# FDC.net
KiCad netlist of a schematic drawn in Altium Designer
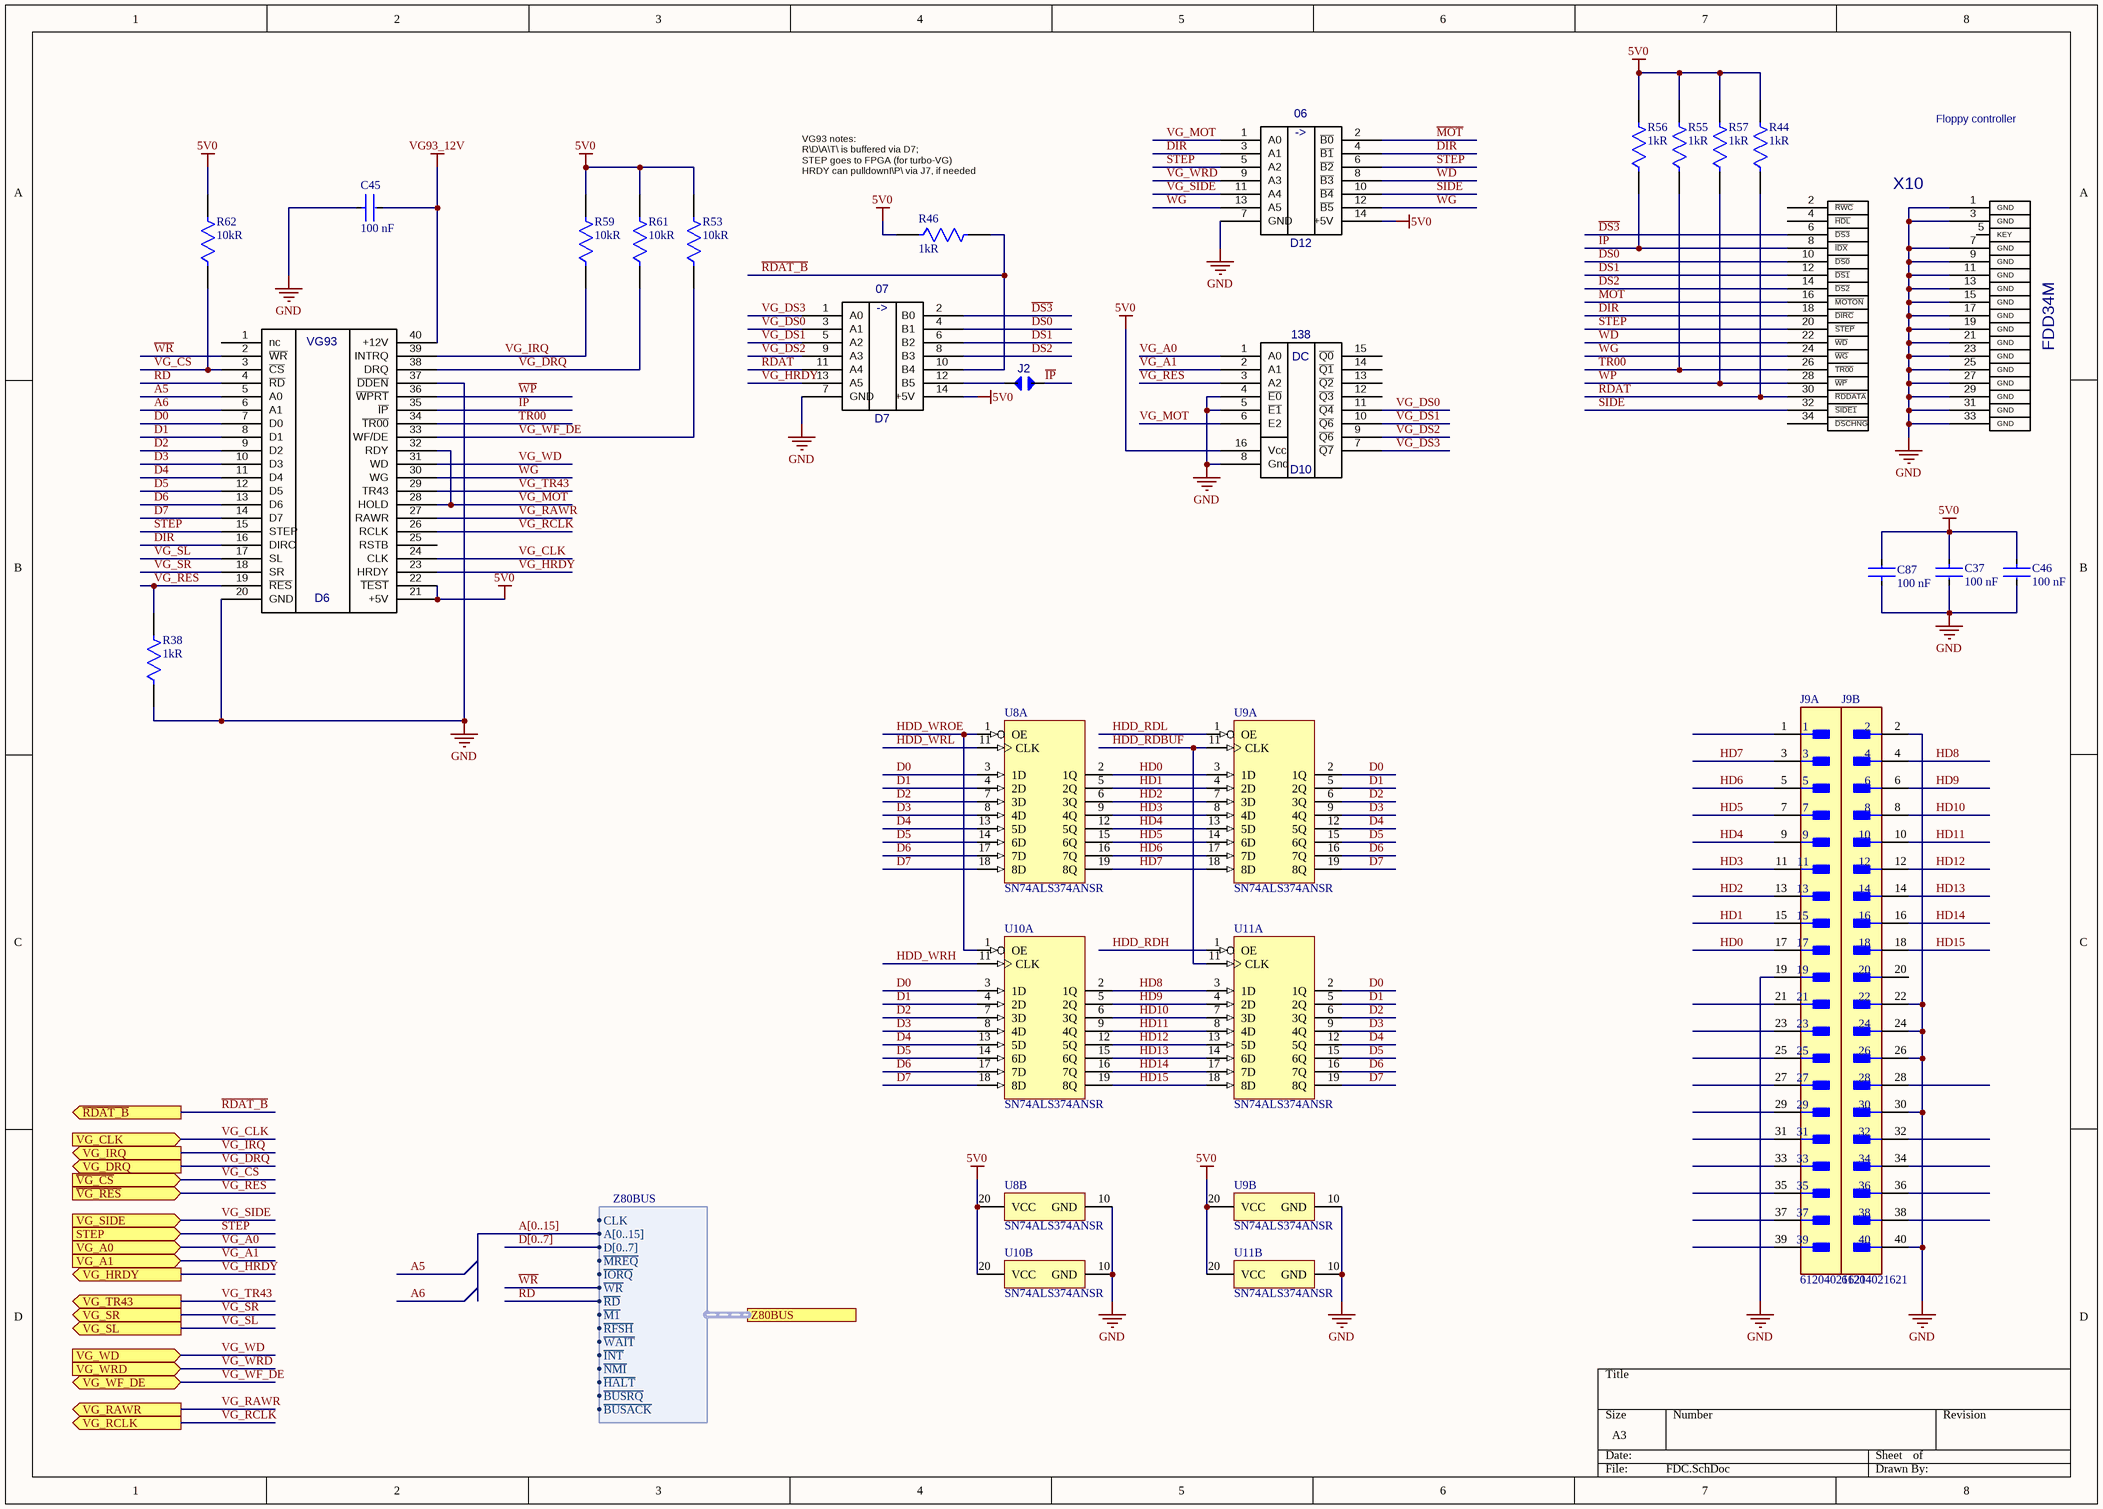
[diagram p0: FDC.SchDoc]

(export (version "E")
  (design (tool "Eeschema 10.0.6"))
  (components
    (comp (ref "C37")
      (value "CC0805KRX7R9BB104")
      (footprint "FP-CC0805-0_85-IPC_A")
      (description "CAP CER 0.1UF 50V X7R 0805")
      (fields (field (name "CAPACITANCE") "100 nF") (field (name "MANUFACTURER") "Yageo"))
      (libsource (lib "SchLib") (part "CMP-2100-03606-3"))
    )
    (comp (ref "C45")
      (value "CC0805KRX7R9BB104")
      (footprint "FP-CC0805-0_85-IPC_A")
      (description "CAP CER 0.1UF 50V X7R 0805")
      (fields (field (name "CAPACITANCE") "100 nF") (field (name "MANUFACTURER") "Yageo"))
      (libsource (lib "SchLib") (part "CMP-2100-03606-3"))
    )
    (comp (ref "C46")
      (value "CC0805KRX7R9BB104")
      (footprint "FP-CC0805-0_85-IPC_A")
      (description "CAP CER 0.1UF 50V X7R 0805")
      (fields (field (name "CAPACITANCE") "100 nF") (field (name "MANUFACTURER") "Yageo"))
      (libsource (lib "SchLib") (part "CMP-2100-03606-3"))
    )
    (comp (ref "C87")
      (value "CC0805KRX7R9BB104")
      (footprint "FP-CC0805-0_85-IPC_A")
      (description "CAP CER 0.1UF 50V X7R 0805")
      (fields (field (name "CAPACITANCE") "100 nF") (field (name "MANUFACTURER") "Yageo"))
      (libsource (lib "SchLib") (part "CMP-2100-03606-3"))
    )
    (comp (ref "D6") (value "KR1818VG93") (footprint "DIP40") (libsource (lib "SchLib") (part "KR1818VG93")))
    (comp (ref "D7") (value "07") (footprint "SO14") (libsource (lib "SchLib") (part "07")))
    (comp (ref "D10") (value "138") (footprint "SO16") (libsource (lib "SchLib") (part "138")))
    (comp (ref "D12") (value "06") (footprint "SO14") (libsource (lib "SchLib") (part "06")))
    (comp (ref "J2")
      (value "JUMPER")
      (footprint "JUMPER_JUMPER(Primary)")
      (description "HLT->~IP")
      (libsource (lib "SchLib") (part "JUMPER"))
    )
    (comp (ref "J9")
      (value "61204021621")
      (footprint "FP-61204021621-MFG")
      (description "CONN HEADER VERT 40POS 2.54MM")
      (libsource (lib "Altium Content Vault") (part "48b0ace1069a9a2e6490059f1444f9e"))
    )
    (comp (ref "R38")
      (value "CRCW08051K00FKEAHP")
      (footprint "FP-CRCW0805-HPe3-IPC_A")
      (description "RES Thick Film, 1kΩ, 1%, 0.5W, 100ppm/°C, 0805")
      (fields (field (name "RESISTANCE") "1kR") (field (name "MANUFACTURER") "Vishay Dale"))
      (libsource (lib "SchLib") (part "CMP-02407-004529-1"))
    )
    (comp (ref "R44")
      (value "CRCW08051K00FKEAHP")
      (footprint "FP-CRCW0805-HPe3-IPC_A")
      (description "RES Thick Film, 1kΩ, 1%, 0.5W, 100ppm/°C, 0805")
      (fields (field (name "RESISTANCE") "1kR") (field (name "MANUFACTURER") "Vishay Dale"))
      (libsource (lib "SchLib") (part "CMP-02407-004529-1"))
    )
    (comp (ref "R46")
      (value "CRCW08051K00FKEAHP")
      (footprint "FP-CRCW0805-HPe3-IPC_A")
      (description "RES Thick Film, 1kΩ, 1%, 0.5W, 100ppm/°C, 0805")
      (fields (field (name "RESISTANCE") "1kR") (field (name "MANUFACTURER") "Vishay Dale"))
      (libsource (lib "SchLib") (part "CMP-02407-004529-1"))
    )
    (comp (ref "R53")
      (value "CR0805-JW-103ELF")
      (footprint "FP-CR0805-IPC_A")
      (description "Thick Film Chip Resistors 0805 10kΩ 0.125W 5% 200ppm/°C")
      (fields (field (name "RESISTANCE") "10kR") (field (name "MANUFACTURER") "Bourns"))
      (libsource (lib "SchLib") (part "CMP-07231-003873-1"))
    )
    (comp (ref "R55")
      (value "CRCW08051K00FKEAHP")
      (footprint "FP-CRCW0805-HPe3-IPC_A")
      (description "RES Thick Film, 1kΩ, 1%, 0.5W, 100ppm/°C, 0805")
      (fields (field (name "RESISTANCE") "1kR") (field (name "MANUFACTURER") "Vishay Dale"))
      (libsource (lib "SchLib") (part "CMP-02407-004529-1"))
    )
    (comp (ref "R56")
      (value "CRCW08051K00FKEAHP")
      (footprint "FP-CRCW0805-HPe3-IPC_A")
      (description "RES Thick Film, 1kΩ, 1%, 0.5W, 100ppm/°C, 0805")
      (fields (field (name "RESISTANCE") "1kR") (field (name "MANUFACTURER") "Vishay Dale"))
      (libsource (lib "SchLib") (part "CMP-02407-004529-1"))
    )
    (comp (ref "R57")
      (value "CRCW08051K00FKEAHP")
      (footprint "FP-CRCW0805-HPe3-IPC_A")
      (description "RES Thick Film, 1kΩ, 1%, 0.5W, 100ppm/°C, 0805")
      (fields (field (name "RESISTANCE") "1kR") (field (name "MANUFACTURER") "Vishay Dale"))
      (libsource (lib "SchLib") (part "CMP-02407-004529-1"))
    )
    (comp (ref "R59")
      (value "CR0805-JW-103ELF")
      (footprint "FP-CR0805-IPC_A")
      (description "Thick Film Chip Resistors 0805 10kΩ 0.125W 5% 200ppm/°C")
      (fields (field (name "RESISTANCE") "10kR") (field (name "MANUFACTURER") "Bourns"))
      (libsource (lib "SchLib") (part "CMP-07231-003873-1"))
    )
    (comp (ref "R61")
      (value "CR0805-JW-103ELF")
      (footprint "FP-CR0805-IPC_A")
      (description "Thick Film Chip Resistors 0805 10kΩ 0.125W 5% 200ppm/°C")
      (fields (field (name "RESISTANCE") "10kR") (field (name "MANUFACTURER") "Bourns"))
      (libsource (lib "SchLib") (part "CMP-07231-003873-1"))
    )
    (comp (ref "R62")
      (value "CR0805-JW-103ELF")
      (footprint "FP-CR0805-IPC_A")
      (description "Thick Film Chip Resistors 0805 10kΩ 0.125W 5% 200ppm/°C")
      (fields (field (name "RESISTANCE") "10kR") (field (name "MANUFACTURER") "Bourns"))
      (libsource (lib "SchLib") (part "CMP-07231-003873-1"))
    )
    (comp (ref "U8")
      (value "SN74ALS374ANSR")
      (footprint "NS0020A_M")
      (description "Octal D-Type Edge Triggered Flip-Flops with 3-State Outputs, NS0020A, LARGE T&R")
      (fields
        (field (name "GENERIC PART NUMBER") "SN74ALS374A")
        (field (name "MANUFACTURER") "Texas Instruments")
      )
      (libsource (lib "Altium Content Vault") (part "TI-CD_SNX4XXXXX374X-20"))
    )
    (comp (ref "U9")
      (value "SN74ALS374ANSR")
      (footprint "NS0020A_M")
      (description "Octal D-Type Edge Triggered Flip-Flops with 3-State Outputs, NS0020A, LARGE T&R")
      (fields
        (field (name "GENERIC PART NUMBER") "SN74ALS374A")
        (field (name "MANUFACTURER") "Texas Instruments")
      )
      (libsource (lib "Altium Content Vault") (part "TI-CD_SNX4XXXXX374X-20"))
    )
    (comp (ref "U10")
      (value "SN74ALS374ANSR")
      (footprint "NS0020A_M")
      (description "Octal D-Type Edge Triggered Flip-Flops with 3-State Outputs, NS0020A, LARGE T&R")
      (fields
        (field (name "GENERIC PART NUMBER") "SN74ALS374A")
        (field (name "MANUFACTURER") "Texas Instruments")
      )
      (libsource (lib "Altium Content Vault") (part "TI-CD_SNX4XXXXX374X-20"))
    )
    (comp (ref "U11")
      (value "SN74ALS374ANSR")
      (footprint "NS0020A_M")
      (description "Octal D-Type Edge Triggered Flip-Flops with 3-State Outputs, NS0020A, LARGE T&R")
      (fields
        (field (name "GENERIC PART NUMBER") "SN74ALS374A")
        (field (name "MANUFACTURER") "Texas Instruments")
      )
      (libsource (lib "Altium Content Vault") (part "TI-CD_SNX4XXXXX374X-20"))
    )
    (comp (ref "X10") (value "FDD34M") (footprint "FDD34M") (libsource (lib "SchLib") (part "FDD34M")))
  )
  (nets
    (net (code "16") (name "/A5") (class "Default")
      (node (ref "D6") (pin "5") (pinfunction "A0_5") (pintype "passive"))
    )
    (net (code "17") (name "/A6") (class "Default")
      (node (ref "D6") (pin "6") (pinfunction "A1_6") (pintype "passive"))
    )
    (net (code "19") (name "/D0") (class "Default")
      (node (ref "D6") (pin "7") (pinfunction "D0_7") (pintype "passive"))
      (node (ref "U10") (pin "3") (pinfunction "1D_3") (pintype "input"))
      (node (ref "U11") (pin "2") (pinfunction "1Q_2") (pintype "tri_state"))
      (node (ref "U8") (pin "3") (pinfunction "1D_3") (pintype "input"))
      (node (ref "U9") (pin "2") (pinfunction "1Q_2") (pintype "tri_state"))
    )
    (net (code "20") (name "/D1") (class "Default")
      (node (ref "D6") (pin "8") (pinfunction "D1_8") (pintype "passive"))
      (node (ref "U10") (pin "4") (pinfunction "2D_4") (pintype "input"))
      (node (ref "U11") (pin "5") (pinfunction "2Q_5") (pintype "tri_state"))
      (node (ref "U8") (pin "4") (pinfunction "2D_4") (pintype "input"))
      (node (ref "U9") (pin "5") (pinfunction "2Q_5") (pintype "tri_state"))
    )
    (net (code "21") (name "/D2") (class "Default")
      (node (ref "D6") (pin "9") (pinfunction "D2_9") (pintype "passive"))
      (node (ref "U10") (pin "7") (pinfunction "3D_7") (pintype "input"))
      (node (ref "U11") (pin "6") (pinfunction "3Q_6") (pintype "tri_state"))
      (node (ref "U8") (pin "7") (pinfunction "3D_7") (pintype "input"))
      (node (ref "U9") (pin "6") (pinfunction "3Q_6") (pintype "tri_state"))
    )
    (net (code "22") (name "/D3") (class "Default")
      (node (ref "D6") (pin "10") (pinfunction "D3_10") (pintype "passive"))
      (node (ref "U10") (pin "8") (pinfunction "4D_8") (pintype "input"))
      (node (ref "U11") (pin "9") (pinfunction "4Q_9") (pintype "tri_state"))
      (node (ref "U8") (pin "8") (pinfunction "4D_8") (pintype "input"))
      (node (ref "U9") (pin "9") (pinfunction "4Q_9") (pintype "tri_state"))
    )
    (net (code "23") (name "/D4") (class "Default")
      (node (ref "D6") (pin "11") (pinfunction "D4_11") (pintype "passive"))
      (node (ref "U10") (pin "13") (pinfunction "5D_13") (pintype "input"))
      (node (ref "U11") (pin "12") (pinfunction "5Q_12") (pintype "tri_state"))
      (node (ref "U8") (pin "13") (pinfunction "5D_13") (pintype "input"))
      (node (ref "U9") (pin "12") (pinfunction "5Q_12") (pintype "tri_state"))
    )
    (net (code "24") (name "/D5") (class "Default")
      (node (ref "D6") (pin "12") (pinfunction "D5_12") (pintype "passive"))
      (node (ref "U10") (pin "14") (pinfunction "6D_14") (pintype "input"))
      (node (ref "U11") (pin "15") (pinfunction "6Q_15") (pintype "tri_state"))
      (node (ref "U8") (pin "14") (pinfunction "6D_14") (pintype "input"))
      (node (ref "U9") (pin "15") (pinfunction "6Q_15") (pintype "tri_state"))
    )
    (net (code "25") (name "/D6") (class "Default")
      (node (ref "D6") (pin "13") (pinfunction "D6_13") (pintype "passive"))
      (node (ref "U10") (pin "17") (pinfunction "7D_17") (pintype "input"))
      (node (ref "U11") (pin "16") (pinfunction "7Q_16") (pintype "tri_state"))
      (node (ref "U8") (pin "17") (pinfunction "7D_17") (pintype "input"))
      (node (ref "U9") (pin "16") (pinfunction "7Q_16") (pintype "tri_state"))
    )
    (net (code "26") (name "/D7") (class "Default")
      (node (ref "D6") (pin "14") (pinfunction "D7_14") (pintype "passive"))
      (node (ref "U10") (pin "18") (pinfunction "8D_18") (pintype "input"))
      (node (ref "U11") (pin "19") (pinfunction "8Q_19") (pintype "tri_state"))
      (node (ref "U8") (pin "18") (pinfunction "8D_18") (pintype "input"))
      (node (ref "U9") (pin "19") (pinfunction "8Q_19") (pintype "tri_state"))
    )
    (net (code "27") (name "/DIR") (class "Default")
      (node (ref "D12") (pin "3") (pinfunction "A1_3") (pintype "passive"))
      (node (ref "D6") (pin "16") (pinfunction "DIRC_16") (pintype "passive"))
    )
    (net (code "28") (name "/HD0") (class "Default")
      (node (ref "J9") (pin "17") (pinfunction "17_17") (pintype "passive"))
      (node (ref "U8") (pin "2") (pinfunction "1Q_2") (pintype "tri_state"))
      (node (ref "U9") (pin "3") (pinfunction "1D_3") (pintype "input"))
    )
    (net (code "29") (name "/HD1") (class "Default")
      (node (ref "J9") (pin "15") (pinfunction "15_15") (pintype "passive"))
      (node (ref "U8") (pin "5") (pinfunction "2Q_5") (pintype "tri_state"))
      (node (ref "U9") (pin "4") (pinfunction "2D_4") (pintype "input"))
    )
    (net (code "30") (name "/HD2") (class "Default")
      (node (ref "J9") (pin "13") (pinfunction "13_13") (pintype "passive"))
      (node (ref "U8") (pin "6") (pinfunction "3Q_6") (pintype "tri_state"))
      (node (ref "U9") (pin "7") (pinfunction "3D_7") (pintype "input"))
    )
    (net (code "31") (name "/HD3") (class "Default")
      (node (ref "J9") (pin "11") (pinfunction "11_11") (pintype "passive"))
      (node (ref "U8") (pin "9") (pinfunction "4Q_9") (pintype "tri_state"))
      (node (ref "U9") (pin "8") (pinfunction "4D_8") (pintype "input"))
    )
    (net (code "32") (name "/HD4") (class "Default")
      (node (ref "J9") (pin "9") (pinfunction "9_9") (pintype "passive"))
      (node (ref "U8") (pin "12") (pinfunction "5Q_12") (pintype "tri_state"))
      (node (ref "U9") (pin "13") (pinfunction "5D_13") (pintype "input"))
    )
    (net (code "33") (name "/HD5") (class "Default")
      (node (ref "J9") (pin "7") (pinfunction "7_7") (pintype "passive"))
      (node (ref "U8") (pin "15") (pinfunction "6Q_15") (pintype "tri_state"))
      (node (ref "U9") (pin "14") (pinfunction "6D_14") (pintype "input"))
    )
    (net (code "34") (name "/HD6") (class "Default")
      (node (ref "J9") (pin "5") (pinfunction "5_5") (pintype "passive"))
      (node (ref "U8") (pin "16") (pinfunction "7Q_16") (pintype "tri_state"))
      (node (ref "U9") (pin "17") (pinfunction "7D_17") (pintype "input"))
    )
    (net (code "35") (name "/HD7") (class "Default")
      (node (ref "J9") (pin "3") (pinfunction "3_3") (pintype "passive"))
      (node (ref "U8") (pin "19") (pinfunction "8Q_19") (pintype "tri_state"))
      (node (ref "U9") (pin "18") (pinfunction "8D_18") (pintype "input"))
    )
    (net (code "36") (name "/HD8") (class "Default")
      (node (ref "J9") (pin "4") (pinfunction "4_4") (pintype "passive"))
      (node (ref "U10") (pin "2") (pinfunction "1Q_2") (pintype "tri_state"))
      (node (ref "U11") (pin "3") (pinfunction "1D_3") (pintype "input"))
    )
    (net (code "37") (name "/HD9") (class "Default")
      (node (ref "J9") (pin "6") (pinfunction "6_6") (pintype "passive"))
      (node (ref "U10") (pin "5") (pinfunction "2Q_5") (pintype "tri_state"))
      (node (ref "U11") (pin "4") (pinfunction "2D_4") (pintype "input"))
    )
    (net (code "38") (name "/HD10") (class "Default")
      (node (ref "J9") (pin "8") (pinfunction "8_8") (pintype "passive"))
      (node (ref "U10") (pin "6") (pinfunction "3Q_6") (pintype "tri_state"))
      (node (ref "U11") (pin "7") (pinfunction "3D_7") (pintype "input"))
    )
    (net (code "39") (name "/HD11") (class "Default")
      (node (ref "J9") (pin "10") (pinfunction "10_10") (pintype "passive"))
      (node (ref "U10") (pin "9") (pinfunction "4Q_9") (pintype "tri_state"))
      (node (ref "U11") (pin "8") (pinfunction "4D_8") (pintype "input"))
    )
    (net (code "40") (name "/HD12") (class "Default")
      (node (ref "J9") (pin "12") (pinfunction "12_12") (pintype "passive"))
      (node (ref "U10") (pin "12") (pinfunction "5Q_12") (pintype "tri_state"))
      (node (ref "U11") (pin "13") (pinfunction "5D_13") (pintype "input"))
    )
    (net (code "41") (name "/HD13") (class "Default")
      (node (ref "J9") (pin "14") (pinfunction "14_14") (pintype "passive"))
      (node (ref "U10") (pin "15") (pinfunction "6Q_15") (pintype "tri_state"))
      (node (ref "U11") (pin "14") (pinfunction "6D_14") (pintype "input"))
    )
    (net (code "42") (name "/HD14") (class "Default")
      (node (ref "J9") (pin "16") (pinfunction "16_16") (pintype "passive"))
      (node (ref "U10") (pin "16") (pinfunction "7Q_16") (pintype "tri_state"))
      (node (ref "U11") (pin "17") (pinfunction "7D_17") (pintype "input"))
    )
    (net (code "43") (name "/HD15") (class "Default")
      (node (ref "J9") (pin "18") (pinfunction "18_18") (pintype "passive"))
      (node (ref "U10") (pin "19") (pinfunction "8Q_19") (pintype "tri_state"))
      (node (ref "U11") (pin "18") (pinfunction "8D_18") (pintype "input"))
    )
    (net (code "44") (name "/HDD_RDBUF") (class "Default")
      (node (ref "U11") (pin "11") (pinfunction "CLK_11") (pintype "input"))
      (node (ref "U9") (pin "11") (pinfunction "CLK_11") (pintype "input"))
    )
    (net (code "45") (name "/HDD_RDH") (class "Default")
      (node (ref "U11") (pin "1") (pinfunction "OE_1") (pintype "input"))
    )
    (net (code "46") (name "/HDD_RDL") (class "Default")
      (node (ref "U9") (pin "1") (pinfunction "OE_1") (pintype "input"))
    )
    (net (code "47") (name "/HDD_WRH") (class "Default")
      (node (ref "U10") (pin "11") (pinfunction "CLK_11") (pintype "input"))
    )
    (net (code "48") (name "/HDD_WRL") (class "Default")
      (node (ref "U8") (pin "11") (pinfunction "CLK_11") (pintype "input"))
    )
    (net (code "49") (name "/HDD_WROE") (class "Default")
      (node (ref "U10") (pin "1") (pinfunction "OE_1") (pintype "input"))
      (node (ref "U8") (pin "1") (pinfunction "OE_1") (pintype "input"))
    )
    (net (code "50") (name "/STEP") (class "Default")
      (node (ref "D12") (pin "5") (pinfunction "A2_5") (pintype "passive"))
      (node (ref "D6") (pin "15") (pinfunction "STEP_15") (pintype "passive"))
    )
    (net (code "51") (name "/VG_A0") (class "Default")
      (node (ref "D10") (pin "1") (pinfunction "A0_1") (pintype "passive"))
    )
    (net (code "52") (name "/VG_A1") (class "Default")
      (node (ref "D10") (pin "2") (pinfunction "A1_2") (pintype "passive"))
    )
    (net (code "53") (name "/VG_CLK") (class "Default")
      (node (ref "D6") (pin "24") (pinfunction "CLK_24") (pintype "passive"))
    )
    (net (code "54") (name "/VG_DRQ") (class "Default")
      (node (ref "D6") (pin "38") (pinfunction "DRQ_38") (pintype "passive"))
      (node (ref "R61") (pin "1") (pinfunction "1_1") (pintype "passive"))
    )
    (net (code "55") (name "/VG_DS0") (class "Default")
      (node (ref "D10") (pin "11") (pinfunction "~{Q4}_11") (pintype "passive"))
      (node (ref "D7") (pin "3") (pinfunction "A1_3") (pintype "passive"))
    )
    (net (code "56") (name "/VG_DS1") (class "Default")
      (node (ref "D10") (pin "10") (pinfunction "~{Q6}_10") (pintype "passive"))
      (node (ref "D7") (pin "5") (pinfunction "A2_5") (pintype "passive"))
    )
    (net (code "57") (name "/VG_DS2") (class "Default")
      (node (ref "D10") (pin "9") (pinfunction "~{Q6}_9") (pintype "passive"))
      (node (ref "D7") (pin "9") (pinfunction "A3_9") (pintype "passive"))
    )
    (net (code "58") (name "/VG_DS3") (class "Default")
      (node (ref "D10") (pin "7") (pinfunction "~{Q7}_7") (pintype "passive"))
      (node (ref "D7") (pin "1") (pinfunction "A0_1") (pintype "passive"))
    )
    (net (code "59") (name "/VG_HRDY") (class "Default")
      (node (ref "D6") (pin "23") (pinfunction "HRDY_23") (pintype "passive"))
      (node (ref "D7") (pin "13") (pinfunction "A5_13") (pintype "passive"))
    )
    (net (code "60") (name "/VG_IRQ") (class "Default")
      (node (ref "D6") (pin "39") (pinfunction "INTRQ_39") (pintype "passive"))
      (node (ref "R59") (pin "1") (pinfunction "1_1") (pintype "passive"))
    )
    (net (code "61") (name "/VG_MOT") (class "Default")
      (node (ref "D10") (pin "6") (pinfunction "E2_6") (pintype "passive"))
      (node (ref "D12") (pin "1") (pinfunction "A0_1") (pintype "passive"))
      (node (ref "D6") (pin "28") (pinfunction "HOLD_28") (pintype "passive"))
      (node (ref "D6") (pin "32") (pinfunction "RDY_32") (pintype "passive"))
    )
    (net (code "62") (name "/VG_RAWR") (class "Default")
      (node (ref "D6") (pin "27") (pinfunction "RAWR_27") (pintype "passive"))
    )
    (net (code "63") (name "/VG_RCLK") (class "Default")
      (node (ref "D6") (pin "26") (pinfunction "RCLK_26") (pintype "passive"))
    )
    (net (code "64") (name "/VG_SIDE") (class "Default")
      (node (ref "D12") (pin "11") (pinfunction "A4_11") (pintype "passive"))
    )
    (net (code "65") (name "/VG_SL") (class "Default")
      (node (ref "D6") (pin "17") (pinfunction "SL_17") (pintype "passive"))
    )
    (net (code "66") (name "/VG_SR") (class "Default")
      (node (ref "D6") (pin "18") (pinfunction "SR_18") (pintype "passive"))
    )
    (net (code "67") (name "/VG_TR43") (class "Default")
      (node (ref "D6") (pin "29") (pinfunction "TR43_29") (pintype "passive"))
    )
    (net (code "68") (name "/VG_WD") (class "Default")
      (node (ref "D6") (pin "31") (pinfunction "WD_31") (pintype "passive"))
    )
    (net (code "69") (name "/VG_WF_DE") (class "Default")
      (node (ref "D6") (pin "33") (pinfunction "WF/DE_33") (pintype "passive"))
      (node (ref "R53") (pin "1") (pinfunction "1_1") (pintype "passive"))
    )
    (net (code "70") (name "/VG_WRD") (class "Default")
      (node (ref "D12") (pin "9") (pinfunction "A3_9") (pintype "passive"))
    )
    (net (code "71") (name "/WG") (class "Default")
      (node (ref "D12") (pin "13") (pinfunction "A5_13") (pintype "passive"))
      (node (ref "D6") (pin "30") (pinfunction "WG_30") (pintype "passive"))
    )
    (net (code "74") (name "/~{DIR}") (class "Default")
      (node (ref "D12") (pin "4") (pinfunction "~{B1}_4") (pintype "passive"))
      (node (ref "X10") (pin "18") (pinfunction "~{DIRC}_18") (pintype "passive"))
    )
    (net (code "75") (name "/~{DS0}") (class "Default")
      (node (ref "D7") (pin "4") (pinfunction "B1_4") (pintype "passive"))
      (node (ref "X10") (pin "10") (pinfunction "~{DS0}_10") (pintype "passive"))
    )
    (net (code "76") (name "/~{DS1}") (class "Default")
      (node (ref "D7") (pin "6") (pinfunction "B2_6") (pintype "passive"))
      (node (ref "X10") (pin "12") (pinfunction "~{DS1}_12") (pintype "passive"))
    )
    (net (code "77") (name "/~{DS2}") (class "Default")
      (node (ref "D7") (pin "8") (pinfunction "B3_8") (pintype "passive"))
      (node (ref "X10") (pin "14") (pinfunction "~{DS2}_14") (pintype "passive"))
    )
    (net (code "78") (name "/~{DS3}") (class "Default")
      (node (ref "D7") (pin "2") (pinfunction "B0_2") (pintype "passive"))
      (node (ref "X10") (pin "6") (pinfunction "~{DS3}_6") (pintype "passive"))
    )
    (net (code "79") (name "/~{IP}") (class "Default")
      (node (ref "D6") (pin "35") (pinfunction "~{IP}_35") (pintype "passive"))
      (node (ref "J2") (pin "1") (pinfunction "2_1") (pintype "passive"))
      (node (ref "R56") (pin "1") (pinfunction "1_1") (pintype "passive"))
      (node (ref "X10") (pin "8") (pinfunction "~{IDX}_8") (pintype "passive"))
    )
    (net (code "80") (name "/~{MOT}") (class "Default")
      (node (ref "D12") (pin "2") (pinfunction "~{B0}_2") (pintype "passive"))
      (node (ref "X10") (pin "16") (pinfunction "~{MOTON}_16") (pintype "passive"))
    )
    (net (code "81") (name "/~{RDAT_B}") (class "Default")
      (node (ref "D7") (pin "10") (pinfunction "B4_10") (pintype "passive"))
      (node (ref "R46") (pin "2") (pinfunction "2_2") (pintype "passive"))
    )
    (net (code "82") (name "/~{RDAT}") (class "Default")
      (node (ref "D7") (pin "11") (pinfunction "A4_11") (pintype "passive"))
      (node (ref "R44") (pin "1") (pinfunction "1_1") (pintype "passive"))
      (node (ref "X10") (pin "30") (pinfunction "~{RDDATA}_30") (pintype "passive"))
    )
    (net (code "83") (name "/~{RD}") (class "Default")
      (node (ref "D6") (pin "4") (pinfunction "~{RD}_4") (pintype "passive"))
    )
    (net (code "84") (name "/~{SIDE}") (class "Default")
      (node (ref "D12") (pin "10") (pinfunction "~{B4}_10") (pintype "passive"))
      (node (ref "X10") (pin "32") (pinfunction "~{SIDE1}_32") (pintype "passive"))
    )
    (net (code "85") (name "/~{STEP}") (class "Default")
      (node (ref "D12") (pin "6") (pinfunction "~{B2}_6") (pintype "passive"))
      (node (ref "X10") (pin "20") (pinfunction "~{STEP}_20") (pintype "passive"))
    )
    (net (code "86") (name "/~{TR00}") (class "Default")
      (node (ref "D6") (pin "34") (pinfunction "~{TR00}_34") (pintype "passive"))
      (node (ref "R55") (pin "1") (pinfunction "1_1") (pintype "passive"))
      (node (ref "X10") (pin "26") (pinfunction "~{TR00}_26") (pintype "passive"))
    )
    (net (code "87") (name "/~{VG_CS}") (class "Default")
      (node (ref "D6") (pin "3") (pinfunction "~{CS}_3") (pintype "passive"))
      (node (ref "R62") (pin "1") (pinfunction "1_1") (pintype "passive"))
    )
    (net (code "88") (name "/~{VG_RES}") (class "Default")
      (node (ref "D10") (pin "3") (pinfunction "A2_3") (pintype "passive"))
      (node (ref "D6") (pin "19") (pinfunction "~{RES}_19") (pintype "passive"))
      (node (ref "R38") (pin "2") (pinfunction "2_2") (pintype "passive"))
    )
    (net (code "89") (name "/~{WD}") (class "Default")
      (node (ref "D12") (pin "8") (pinfunction "~{B3}_8") (pintype "passive"))
      (node (ref "X10") (pin "22") (pinfunction "~{WD}_22") (pintype "passive"))
    )
    (net (code "90") (name "/~{WG}") (class "Default")
      (node (ref "D12") (pin "12") (pinfunction "~{B5}_12") (pintype "passive"))
      (node (ref "X10") (pin "24") (pinfunction "~{WG}_24") (pintype "passive"))
    )
    (net (code "91") (name "/~{WP}") (class "Default")
      (node (ref "D6") (pin "36") (pinfunction "~{WPRT}_36") (pintype "passive"))
      (node (ref "R57") (pin "1") (pinfunction "1_1") (pintype "passive"))
      (node (ref "X10") (pin "28") (pinfunction "~{WP}_28") (pintype "passive"))
    )
    (net (code "92") (name "/~{WR}") (class "Default")
      (node (ref "D6") (pin "2") (pinfunction "~{WR}_2") (pintype "passive"))
    )
    (net (code "93") (name "5V0") (class "Default")
      (node (ref "C37") (pin "1") (pinfunction "1_1") (pintype "passive"))
      (node (ref "C46") (pin "1") (pinfunction "1_1") (pintype "passive"))
      (node (ref "C87") (pin "2") (pinfunction "2_2") (pintype "passive"))
      (node (ref "D10") (pin "16") (pinfunction "Vcc_16") (pintype "passive"))
      (node (ref "D12") (pin "14") (pinfunction "+5V_14") (pintype "passive"))
      (node (ref "D6") (pin "21") (pinfunction "+5V_21") (pintype "passive"))
      (node (ref "D6") (pin "22") (pinfunction "~{TEST}_22") (pintype "passive"))
      (node (ref "D7") (pin "14") (pinfunction "+5V_14") (pintype "passive"))
      (node (ref "R44") (pin "2") (pinfunction "2_2") (pintype "passive"))
      (node (ref "R46") (pin "1") (pinfunction "1_1") (pintype "passive"))
      (node (ref "R53") (pin "2") (pinfunction "2_2") (pintype "passive"))
      (node (ref "R55") (pin "2") (pinfunction "2_2") (pintype "passive"))
      (node (ref "R56") (pin "2") (pinfunction "2_2") (pintype "passive"))
      (node (ref "R57") (pin "2") (pinfunction "2_2") (pintype "passive"))
      (node (ref "R59") (pin "2") (pinfunction "2_2") (pintype "passive"))
      (node (ref "R61") (pin "2") (pinfunction "2_2") (pintype "passive"))
      (node (ref "R62") (pin "2") (pinfunction "2_2") (pintype "passive"))
      (node (ref "U10") (pin "20") (pinfunction "VCC_20") (pintype "power_in"))
      (node (ref "U11") (pin "20") (pinfunction "VCC_20") (pintype "power_in"))
      (node (ref "U8") (pin "20") (pinfunction "VCC_20") (pintype "power_in"))
      (node (ref "U9") (pin "20") (pinfunction "VCC_20") (pintype "power_in"))
    )
    (net (code "94") (name "GND") (class "Default")
      (node (ref "C37") (pin "2") (pinfunction "2_2") (pintype "passive"))
      (node (ref "C45") (pin "1") (pinfunction "1_1") (pintype "passive"))
      (node (ref "C46") (pin "2") (pinfunction "2_2") (pintype "passive"))
      (node (ref "C87") (pin "1") (pinfunction "1_1") (pintype "passive"))
      (node (ref "D10") (pin "4") (pinfunction "~{E0}_4") (pintype "passive"))
      (node (ref "D10") (pin "5") (pinfunction "~{E1}_5") (pintype "passive"))
      (node (ref "D10") (pin "8") (pinfunction "Gnd_8") (pintype "passive"))
      (node (ref "D12") (pin "7") (pinfunction "GND_7") (pintype "passive"))
      (node (ref "D6") (pin "20") (pinfunction "GND_20") (pintype "passive"))
      (node (ref "D6") (pin "37") (pinfunction "~{DDEN}_37") (pintype "passive"))
      (node (ref "D7") (pin "7") (pinfunction "GND_7") (pintype "passive"))
      (node (ref "J9") (pin "19") (pinfunction "19_19") (pintype "passive"))
      (node (ref "J9") (pin "2") (pinfunction "2_2") (pintype "passive"))
      (node (ref "J9") (pin "22") (pinfunction "22_22") (pintype "passive"))
      (node (ref "J9") (pin "24") (pinfunction "24_24") (pintype "passive"))
      (node (ref "J9") (pin "26") (pinfunction "26_26") (pintype "passive"))
      (node (ref "J9") (pin "30") (pinfunction "30_30") (pintype "passive"))
      (node (ref "J9") (pin "40") (pinfunction "40_40") (pintype "passive"))
      (node (ref "R38") (pin "1") (pinfunction "1_1") (pintype "passive"))
      (node (ref "U10") (pin "10") (pinfunction "GND_10") (pintype "power_in"))
      (node (ref "U11") (pin "10") (pinfunction "GND_10") (pintype "power_in"))
      (node (ref "U8") (pin "10") (pinfunction "GND_10") (pintype "power_in"))
      (node (ref "U9") (pin "10") (pinfunction "GND_10") (pintype "power_in"))
      (node (ref "X10") (pin "1") (pinfunction "GND_1") (pintype "passive"))
      (node (ref "X10") (pin "11") (pinfunction "GND_11") (pintype "passive"))
      (node (ref "X10") (pin "13") (pinfunction "GND_13") (pintype "passive"))
      (node (ref "X10") (pin "15") (pinfunction "GND_15") (pintype "passive"))
      (node (ref "X10") (pin "17") (pinfunction "GND_17") (pintype "passive"))
      (node (ref "X10") (pin "19") (pinfunction "GND_19") (pintype "passive"))
      (node (ref "X10") (pin "21") (pinfunction "GND_21") (pintype "passive"))
      (node (ref "X10") (pin "23") (pinfunction "GND_23") (pintype "passive"))
      (node (ref "X10") (pin "25") (pinfunction "GND_25") (pintype "passive"))
      (node (ref "X10") (pin "27") (pinfunction "GND_27") (pintype "passive"))
      (node (ref "X10") (pin "29") (pinfunction "GND_29") (pintype "passive"))
      (node (ref "X10") (pin "3") (pinfunction "GND_3") (pintype "passive"))
      (node (ref "X10") (pin "31") (pinfunction "GND_31") (pintype "passive"))
      (node (ref "X10") (pin "33") (pinfunction "GND_33") (pintype "passive"))
      (node (ref "X10") (pin "7") (pinfunction "GND_7") (pintype "passive"))
      (node (ref "X10") (pin "9") (pinfunction "GND_9") (pintype "passive"))
    )
    (net (code "95") (name "Net-(D7-B5)") (class "Default")
      (node (ref "D7") (pin "12") (pinfunction "B5_12") (pintype "passive"))
      (node (ref "J2") (pin "0") (pinfunction "1_0") (pintype "passive"))
    )
    (net (code "96") (name "VG93_12V") (class "Default")
      (node (ref "C45") (pin "2") (pinfunction "2_2") (pintype "passive"))
      (node (ref "D6") (pin "40") (pinfunction "+12V_40") (pintype "passive"))
    )
    (net (code "97") (name "unconnected-(D6-RSTB-Pad25)") (class "Default")
      (node (ref "D6") (pin "25") (pinfunction "RSTB_25") (pintype "passive"))
    )
    (net (code "98") (name "unconnected-(D6-nc-Pad1)") (class "Default")
      (node (ref "D6") (pin "1") (pinfunction "nc_1") (pintype "passive"))
    )
    (net (code "99") (name "unconnected-(D10-~{Q0}-Pad15)") (class "Default")
      (node (ref "D10") (pin "15") (pinfunction "~{Q0}_15") (pintype "passive"))
    )
    (net (code "100") (name "unconnected-(D10-~{Q1}-Pad14)") (class "Default")
      (node (ref "D10") (pin "14") (pinfunction "~{Q1}_14") (pintype "passive"))
    )
    (net (code "101") (name "unconnected-(D10-~{Q2}-Pad13)") (class "Default")
      (node (ref "D10") (pin "13") (pinfunction "~{Q2}_13") (pintype "passive"))
    )
    (net (code "102") (name "unconnected-(D10-~{Q3}-Pad12)") (class "Default")
      (node (ref "D10") (pin "12") (pinfunction "~{Q3}_12") (pintype "passive"))
    )
    (net (code "103") (name "unconnected-(J9-Pad1)") (class "Default")
      (node (ref "J9") (pin "1") (pinfunction "1_1") (pintype "passive"))
    )
    (net (code "104") (name "unconnected-(J9-Pad20)") (class "Default")
      (node (ref "J9") (pin "20") (pinfunction "20_20") (pintype "passive"))
    )
    (net (code "105") (name "unconnected-(J9-Pad21)") (class "Default")
      (node (ref "J9") (pin "21") (pinfunction "21_21") (pintype "passive"))
    )
    (net (code "106") (name "unconnected-(J9-Pad23)") (class "Default")
      (node (ref "J9") (pin "23") (pinfunction "23_23") (pintype "passive"))
    )
    (net (code "107") (name "unconnected-(J9-Pad25)") (class "Default")
      (node (ref "J9") (pin "25") (pinfunction "25_25") (pintype "passive"))
    )
    (net (code "108") (name "unconnected-(J9-Pad27)") (class "Default")
      (node (ref "J9") (pin "27") (pinfunction "27_27") (pintype "passive"))
    )
    (net (code "109") (name "unconnected-(J9-Pad28)") (class "Default")
      (node (ref "J9") (pin "28") (pinfunction "28_28") (pintype "passive"))
    )
    (net (code "110") (name "unconnected-(J9-Pad29)") (class "Default")
      (node (ref "J9") (pin "29") (pinfunction "29_29") (pintype "passive"))
    )
    (net (code "111") (name "unconnected-(J9-Pad31)") (class "Default")
      (node (ref "J9") (pin "31") (pinfunction "31_31") (pintype "passive"))
    )
    (net (code "112") (name "unconnected-(J9-Pad32)") (class "Default")
      (node (ref "J9") (pin "32") (pinfunction "32_32") (pintype "passive"))
    )
    (net (code "113") (name "unconnected-(J9-Pad33)") (class "Default")
      (node (ref "J9") (pin "33") (pinfunction "33_33") (pintype "passive"))
    )
    (net (code "114") (name "unconnected-(J9-Pad34)") (class "Default")
      (node (ref "J9") (pin "34") (pinfunction "34_34") (pintype "passive"))
    )
    (net (code "115") (name "unconnected-(J9-Pad35)") (class "Default")
      (node (ref "J9") (pin "35") (pinfunction "35_35") (pintype "passive"))
    )
    (net (code "116") (name "unconnected-(J9-Pad36)") (class "Default")
      (node (ref "J9") (pin "36") (pinfunction "36_36") (pintype "passive"))
    )
    (net (code "117") (name "unconnected-(J9-Pad37)") (class "Default")
      (node (ref "J9") (pin "37") (pinfunction "37_37") (pintype "passive"))
    )
    (net (code "118") (name "unconnected-(J9-Pad38)") (class "Default")
      (node (ref "J9") (pin "38") (pinfunction "38_38") (pintype "passive"))
    )
    (net (code "119") (name "unconnected-(J9-Pad39)") (class "Default")
      (node (ref "J9") (pin "39") (pinfunction "39_39") (pintype "passive"))
    )
    (net (code "120") (name "unconnected-(X10-KEY-Pad5)") (class "Default")
      (node (ref "X10") (pin "5") (pinfunction "KEY_5") (pintype "passive"))
    )
    (net (code "121") (name "unconnected-(X10-~{DSCHNG}-Pad34)") (class "Default")
      (node (ref "X10") (pin "34") (pinfunction "~{DSCHNG}_34") (pintype "passive"))
    )
    (net (code "122") (name "unconnected-(X10-~{HDL}-Pad4)") (class "Default")
      (node (ref "X10") (pin "4") (pinfunction "~{HDL}_4") (pintype "passive"))
    )
    (net (code "123") (name "unconnected-(X10-~{RWC}-Pad2)") (class "Default")
      (node (ref "X10") (pin "2") (pinfunction "~{RWC}_2") (pintype "passive"))
    )
  )
)
